# CONNECTORS_SELECTORS.net
KiCad netlist of a schematic drawn in Altium Designer
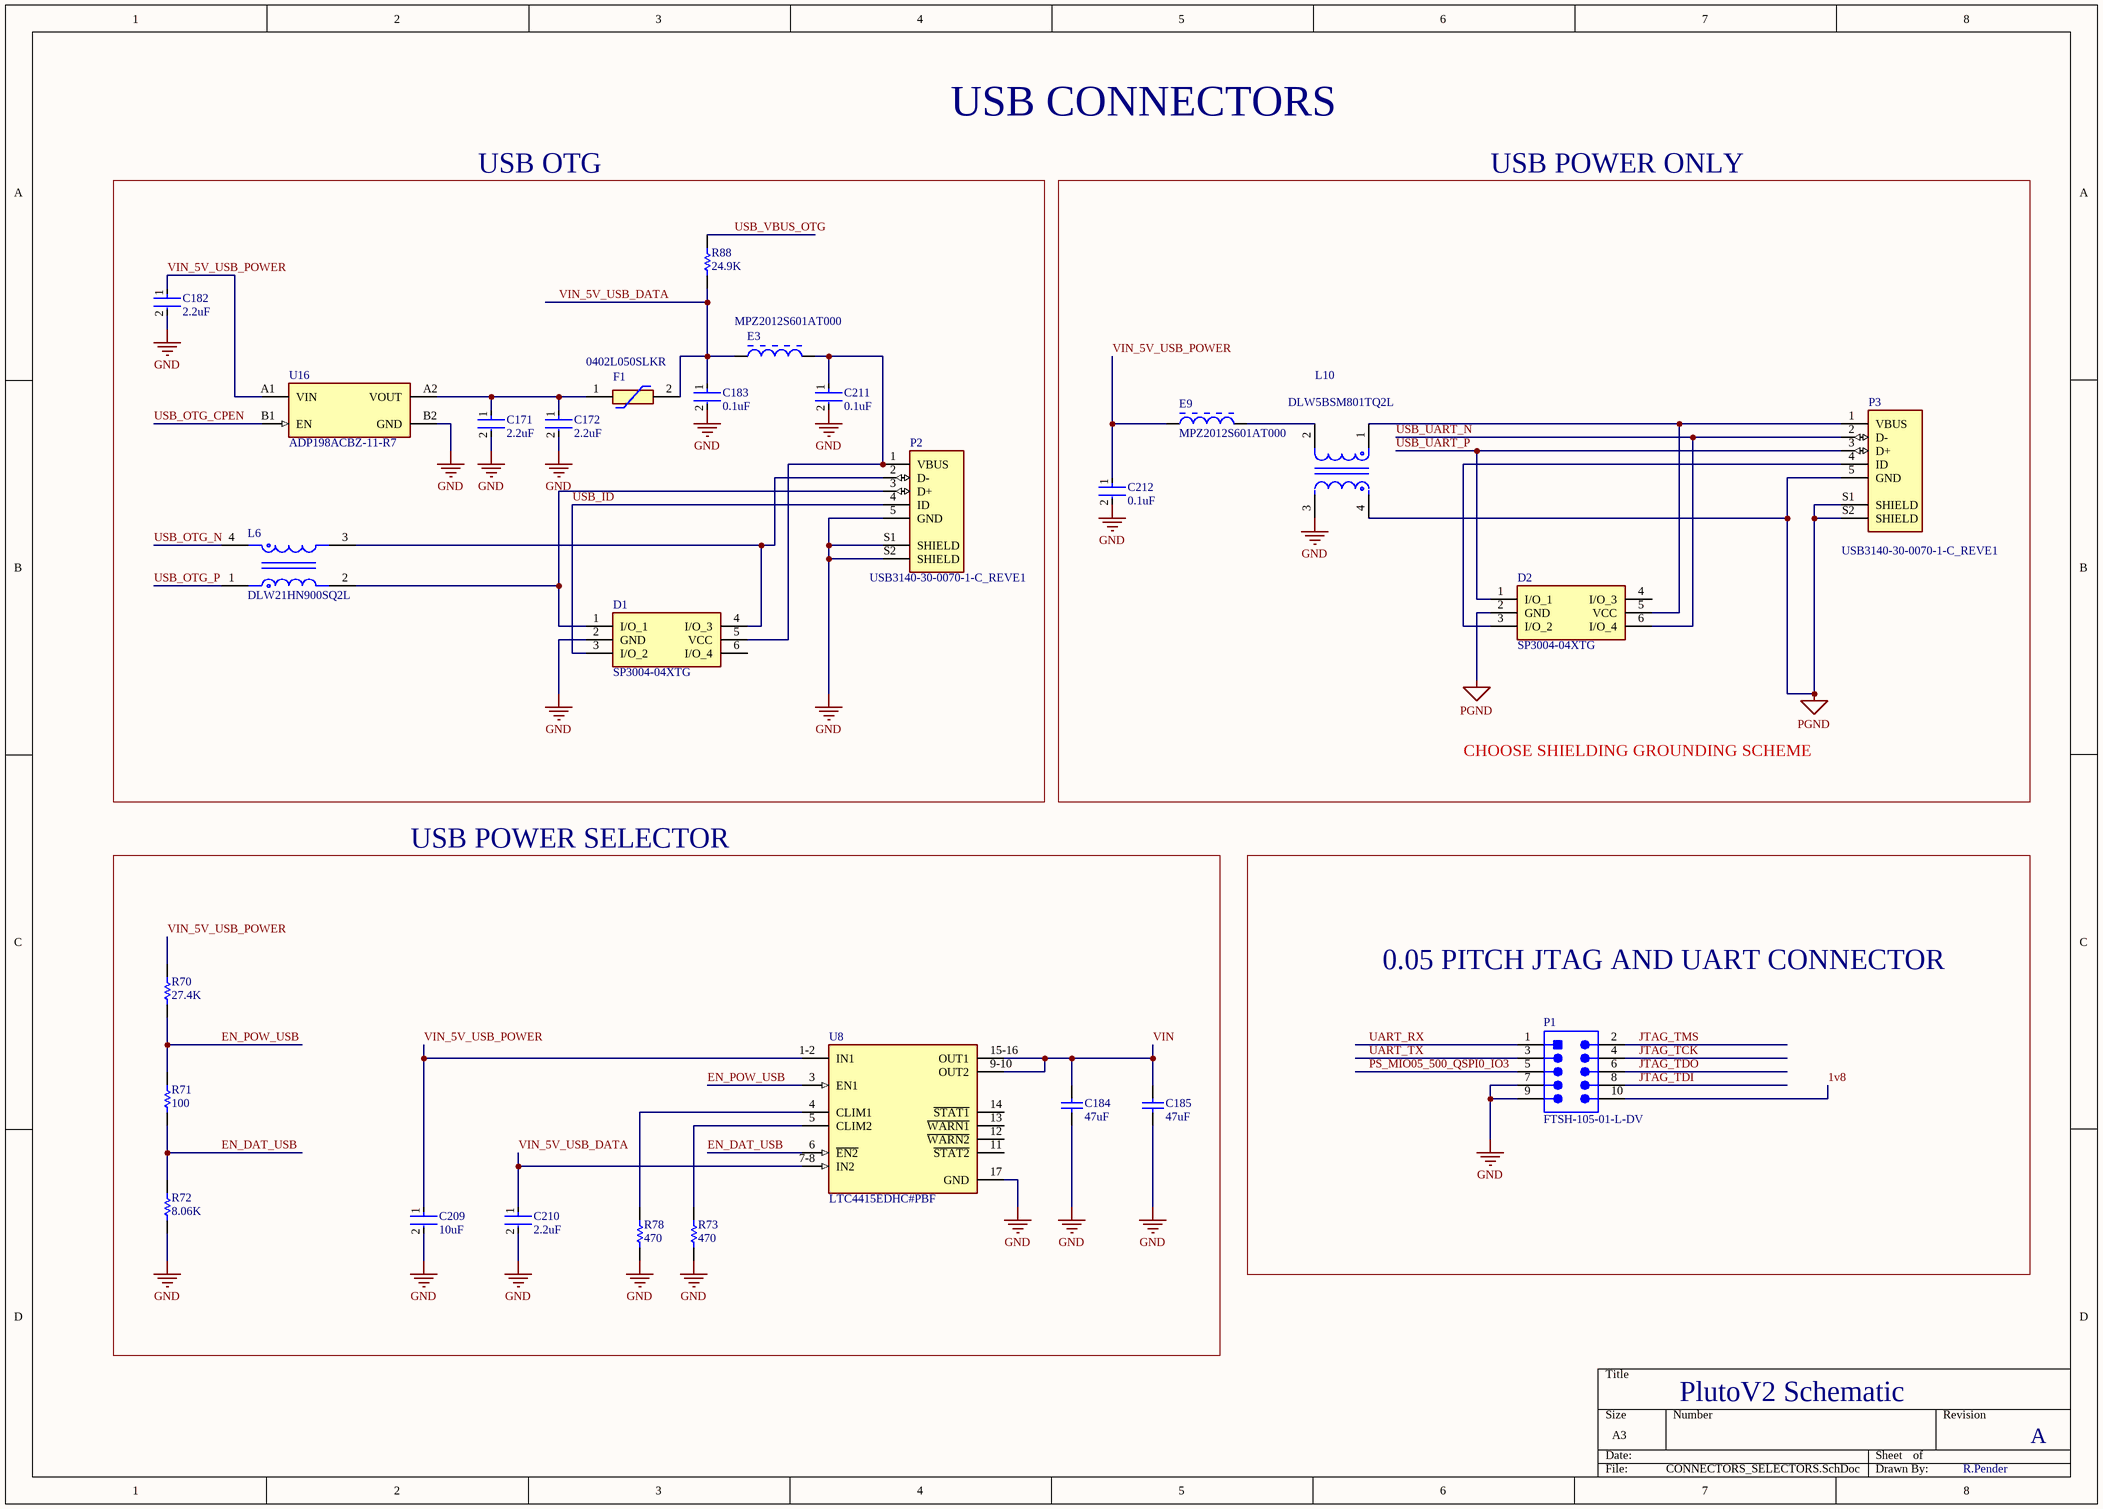
[diagram p0: CONNECTORS_SELECTORS.SchDoc]

(export (version "E")
  (design (tool "Eeschema 10.0.6"))
  (components
    (comp (ref "C171")
      (value "2.2uF")
      (footprint "FP-GRM188-0_2-IPC_C")
      (description "Chip Multilayer Ceramic Capacitors for General Purpose, 0603, 2.2uF, X5R, 15%, 10%, 50V")
      (fields (field (name "TOLERANCE") "10%"))
      (libsource (lib "Altium Content Vault") (part "11868f565c42a9108669ba33697ecf6"))
    )
    (comp (ref "C172")
      (value "2.2uF")
      (footprint "FP-GRM188-0_2-IPC_C")
      (description "Chip Multilayer Ceramic Capacitors for General Purpose, 0603, 2.2uF, X5R, 15%, 10%, 50V")
      (fields (field (name "TOLERANCE") "10%"))
      (libsource (lib "Altium Content Vault") (part "11868f565c42a9108669ba33697ecf6"))
    )
    (comp (ref "C182")
      (value "2.2uF")
      (footprint "FP-GRM188-0_2-MFG")
      (description "Chip Multilayer Ceramic Capacitors for General Purpose, 0603, 2.2uF, X5R, 15%, 10%, 50V")
      (fields (field (name "TOLERANCE") "10%"))
      (libsource (lib "Altium Content Vault") (part "11868f565c42a9108669ba33697ecf6"))
    )
    (comp (ref "C183")
      (value "0.1uF")
      (footprint "FP-CL10-IPC_A")
      (description "Cap Ceramic 100nF 100V X7R ±10% Pad SMD 0603 +125°C T/R")
      (fields (field (name "TOLERANCE") "10%"))
      (libsource (lib "Altium Content Vault") (part "b4654b650e69147ec39a6b967a45e02"))
    )
    (comp (ref "C184")
      (value "47uF")
      (footprint "TAYO-JMK212BBJ476MG-T_L")
      (fields
        (field (name "MANUFACTURER") "Taiyo Yuden")
        (field (name "TOLERANCE") "±20%")
        (field (name "PCN PART NUMBER") "X5R,X7RDielectrics23/Jan/2008")
      )
      (libsource (lib "Altium Content Vault") (part "CAP-NP-2"))
    )
    (comp (ref "C185")
      (value "47uF")
      (footprint "TAYO-JMK212BBJ476MG-T_L")
      (fields
        (field (name "MANUFACTURER") "Taiyo Yuden")
        (field (name "TOLERANCE") "±20%")
        (field (name "PCN PART NUMBER") "X5R,X7RDielectrics23/Jan/2008")
      )
      (libsource (lib "Altium Content Vault") (part "CAP-NP-2"))
    )
    (comp (ref "C209")
      (value "10uF")
      (footprint "FP-GRM188-0_15-MFG")
      (description "Chip Multilayer Ceramic Capacitors for General Purpose, 0603, 10uF, X5R, 15%, 20%, 10V")
      (fields (field (name "TOLERANCE") "20%"))
      (libsource (lib "Altium Content Vault") (part "02cd4be3c70576c341d710602a673aa"))
    )
    (comp (ref "C210")
      (value "2.2uF")
      (footprint "FP-GRM188-0_2-IPC_C")
      (description "Chip Multilayer Ceramic Capacitors for General Purpose, 0603, 2.2uF, X5R, 15%, 10%, 50V")
      (fields (field (name "TOLERANCE") "10%"))
      (libsource (lib "Altium Content Vault") (part "11868f565c42a9108669ba33697ecf6"))
    )
    (comp (ref "C211")
      (value "0.1uF")
      (footprint "FP-CL10-IPC_A")
      (description "Cap Ceramic 100nF 100V X7R ±10% Pad SMD 0603 +125°C T/R")
      (fields (field (name "TOLERANCE") "10%"))
      (libsource (lib "Altium Content Vault") (part "b4654b650e69147ec39a6b967a45e02"))
    )
    (comp (ref "C212")
      (value "0.1uF")
      (footprint "FP-CL10-IPC_A")
      (description "Cap Ceramic 100nF 100V X7R ±10% Pad SMD 0603 +125°C T/R")
      (fields (field (name "TOLERANCE") "10%"))
      (libsource (lib "Altium Content Vault") (part "b4654b650e69147ec39a6b967a45e02"))
    )
    (comp (ref "D1")
      (value "SP3004-04XTG")
      (footprint "SamacSys:SOTFL50P160X60-6N")
      (description "TVS Diode (Uni-directional)")
      (libsource (lib "*") (part "SP3004-04XTG"))
    )
    (comp (ref "D2")
      (value "SP3004-04XTG")
      (footprint "SamacSys:SOTFL50P160X60-6N")
      (description "TVS Diode (Uni-directional)")
      (libsource (lib "*") (part "SP3004-04XTG"))
    )
    (comp (ref "E3")
      (value "MPZ2012S601AT000")
      (footprint "TDK-MPZ2012_V")
      (description "Chip Bead, 0.1 Ohm, 2 A, -55 to 125 degC, 2-Pin SMD (0805), RoHS, Tape and Reel")
      (fields (field (name "PCN PART NUMBER") "MMZ,MPSSeriesOct/2014") (field (name "MANUFACTURER") "TDK"))
      (libsource (lib "Altium Content Vault") (part "BEAD-2"))
    )
    (comp (ref "E9")
      (value "MPZ2012S601AT000")
      (footprint "TDK-MPZ2012_V")
      (description "Chip Bead, 0.1 Ohm, 2 A, -55 to 125 degC, 2-Pin SMD (0805), RoHS, Tape and Reel")
      (fields (field (name "PCN PART NUMBER") "MMZ,MPSSeriesOct/2014") (field (name "MANUFACTURER") "TDK"))
      (libsource (lib "Altium Content Vault") (part "BEAD-2"))
    )
    (comp (ref "F1")
      (value "0402L050SLKR")
      (footprint "SamacSys:0402L010SLKR")
      (description "Resettable Fuse")
      (libsource (lib "*") (part "0402L050SLKR"))
    )
    (comp (ref "L6")
      (value "DLW21HN900SQ2L")
      (footprint "FP-DLW21HN-MFG")
      (description "CMC 330MA 2LN 90 OHM SMD")
      (fields (field (name "TOLERANCE") "25%"))
      (libsource (lib "Altium Content Vault") (part "0a69a9865a8fa8fb197e9315ef85d0a"))
    )
    (comp (ref "L10")
      (value "DLW5BSM801TQ2L")
      (footprint "FP-DLW5BS-MFG")
      (description "Common Mode Choke, 2020, 800Ω @ 100MHz, 0.056Ω, 40%, 2A")
      (fields (field (name "TOLERANCE") "40%"))
      (libsource (lib "Altium Content Vault") (part "7e18bf8fdb9f2485ca2bcdf9073d69f"))
    )
    (comp (ref "P1")
      (value "FTSH-105-01-L-DV")
      (footprint "SMTC-FTSH-105-01-L-DV_V")
      (description "Male Header, Pitch 1.27 mm, 2 x 5 Position, Height 5.96 mm, -55 to 125 degC, RoHS, Bulk")
      (fields (field (name "MANUFACTURER") "Samtec"))
      (libsource (lib "Altium Content Vault") (part "CN-2P-M-R10"))
    )
    (comp (ref "P2")
      (value "USB3140-30-0070-1-C_REVE1")
      (footprint "GCT_USB3140-30-0070-1-C_REVE1")
      (fields (field (name "MF") "Global Connector Technology") (field (name "MP") "USB3140-30-0070-1-C"))
      (libsource (lib "USB3140-30-0070-1-C_REVE1") (part "USB3140-30-0070-1-C_REVE1"))
    )
    (comp (ref "P3")
      (value "USB3140-30-0070-1-C_REVE1")
      (footprint "GCT_USB3140-30-0070-1-C_REVE1")
      (fields (field (name "MF") "Global Connector Technology") (field (name "MP") "USB3140-30-0070-1-C"))
      (libsource (lib "USB3140-30-0070-1-C_REVE1") (part "USB3140-30-0070-1-C_REVE1"))
    )
    (comp (ref "R70")
      (value "27.4K")
      (footprint "2-0402")
      (fields (field (name "PUBLISHER") "Altium Limited"))
      (libsource (lib "Panasonic Resistor") (part "ERJ2RK"))
    )
    (comp (ref "R71")
      (value "100")
      (footprint "2-0402")
      (fields (field (name "PUBLISHER") "Altium Limited"))
      (libsource (lib "Panasonic Resistor") (part "ERJ2RK"))
    )
    (comp (ref "R72")
      (value "8.06K")
      (footprint "2-0402")
      (fields (field (name "PUBLISHER") "Altium Limited"))
      (libsource (lib "Panasonic Resistor") (part "ERJ2RK"))
    )
    (comp (ref "R73")
      (value "470")
      (footprint "RESC1005X40X25ML05T10")
      (fields (field (name "PART NUMBER") "RC0402FR-07470RL") (field (name "MANUFACTURER") "Yageo / Phycomp"))
      (libsource (lib "Altium Content Vault") (part "RES"))
    )
    (comp (ref "R78")
      (value "470")
      (footprint "RESC1005X40X25ML05T10")
      (fields (field (name "PART NUMBER") "RC0402FR-07470RL") (field (name "MANUFACTURER") "Yageo / Phycomp"))
      (libsource (lib "Altium Content Vault") (part "RES"))
    )
    (comp (ref "R88")
      (value "24.9K")
      (footprint "2-0402")
      (fields (field (name "PUBLISHER") "Altium Limited"))
      (libsource (lib "Panasonic Resistor") (part "ERJ2RK"))
    )
    (comp (ref "U8")
      (value "LTC4415EDHC#PBF")
      (footprint "FP-DHC-16-05-08-1872-MFG")
      (description "IC OR CTRLR SRC SELECT 16DFN")
      (libsource (lib "Altium Content Vault") (part "3ca062e251a206593296efba02ab3fb"))
    )
    (comp (ref "U16")
      (value "ADP198ACBZ-11-R7")
      (footprint "FP-CB-4-4-MFG")
      (description "IC PWR SWITCH P-CHAN 1:1 4WLCSP")
      (libsource (lib "Altium Content Vault") (part "e79baadf0d63db38dbad7ddd3c26481"))
    )
  )
  (nets
    (net (code "1") (name "/1v8") (class "Default")
      (node (ref "P1") (pin "10") (pinfunction "10_10") (pintype "passive"))
    )
    (net (code "2") (name "/EN_DAT_USB") (class "Default")
      (node (ref "R71") (pin "2") (pinfunction "2_2") (pintype "passive"))
      (node (ref "R72") (pin "1") (pinfunction "1_1") (pintype "passive"))
      (node (ref "U8") (pin "6") (pinfunction "~{EN2}_6") (pintype "input"))
    )
    (net (code "3") (name "/EN_POW_USB") (class "Default")
      (node (ref "R70") (pin "2") (pinfunction "2_2") (pintype "passive"))
      (node (ref "R71") (pin "1") (pinfunction "1_1") (pintype "passive"))
      (node (ref "U8") (pin "3") (pinfunction "EN1_3") (pintype "input"))
    )
    (net (code "4") (name "/JTAG_TCK") (class "Default")
      (node (ref "P1") (pin "4") (pinfunction "4_4") (pintype "passive"))
    )
    (net (code "5") (name "/JTAG_TDI") (class "Default")
      (node (ref "P1") (pin "8") (pinfunction "8_8") (pintype "passive"))
    )
    (net (code "6") (name "/JTAG_TDO") (class "Default")
      (node (ref "P1") (pin "6") (pinfunction "6_6") (pintype "passive"))
    )
    (net (code "7") (name "/JTAG_TMS") (class "Default")
      (node (ref "P1") (pin "2") (pinfunction "2_2") (pintype "passive"))
    )
    (net (code "8") (name "/PS_MIO05_500_QSPI0_IO3") (class "Default")
      (node (ref "P1") (pin "5") (pinfunction "5_5") (pintype "passive"))
    )
    (net (code "9") (name "/UART_RX") (class "Default")
      (node (ref "P1") (pin "1") (pinfunction "1_1") (pintype "passive"))
    )
    (net (code "10") (name "/UART_TX") (class "Default")
      (node (ref "P1") (pin "3") (pinfunction "3_3") (pintype "passive"))
    )
    (net (code "11") (name "/USB_ID") (class "Default")
      (node (ref "D1") (pin "3") (pinfunction "I/O_2_3") (pintype "passive"))
      (node (ref "P2") (pin "4") (pinfunction "ID_4") (pintype "passive"))
    )
    (net (code "12") (name "/USB_OTG_CPEN") (class "Default")
      (node (ref "U16") (pin "B1") (pinfunction "EN_B1") (pintype "input"))
    )
    (net (code "13") (name "/USB_OTG_N") (class "Default")
      (node (ref "L6") (pin "4") (pinfunction "4_4") (pintype "passive"))
    )
    (net (code "14") (name "/USB_OTG_P") (class "Default")
      (node (ref "L6") (pin "1") (pinfunction "1_1") (pintype "passive"))
    )
    (net (code "15") (name "/USB_UART_N") (class "Default")
      (node (ref "D2") (pin "6") (pinfunction "I/O_4_6") (pintype "passive"))
      (node (ref "P3") (pin "2") (pinfunction "D-_2") (pintype "bidirectional"))
    )
    (net (code "16") (name "/USB_UART_P") (class "Default")
      (node (ref "D2") (pin "1") (pinfunction "I/O_1_1") (pintype "passive"))
      (node (ref "P3") (pin "3") (pinfunction "D+_3") (pintype "bidirectional"))
    )
    (net (code "17") (name "/USB_VBUS_OTG") (class "Default")
      (node (ref "R88") (pin "2") (pinfunction "2_2") (pintype "passive"))
    )
    (net (code "18") (name "/VIN") (class "Default")
      (node (ref "C184") (pin "1") (pinfunction "1_1") (pintype "passive"))
      (node (ref "C185") (pin "1") (pinfunction "1_1") (pintype "passive"))
      (node (ref "U8") (pin "15-16") (pinfunction "OUT1_15-16") (pintype "passive"))
      (node (ref "U8") (pin "9-10") (pinfunction "OUT2_9-10") (pintype "passive"))
    )
    (net (code "19") (name "/VIN_5V_USB_DATA") (class "Default")
      (node (ref "C183") (pin "1") (pinfunction "1_1") (pintype "passive"))
      (node (ref "C210") (pin "1") (pinfunction "1_1") (pintype "passive"))
      (node (ref "E3") (pin "1") (pinfunction "1_1") (pintype "passive"))
      (node (ref "F1") (pin "2") (pinfunction "2_2") (pintype "passive"))
      (node (ref "R88") (pin "1") (pinfunction "1_1") (pintype "passive"))
      (node (ref "U8") (pin "7-8") (pinfunction "IN2_7-8") (pintype "input"))
    )
    (net (code "20") (name "/VIN_5V_USB_POWER") (class "Default")
      (node (ref "C182") (pin "1") (pinfunction "1_1") (pintype "passive"))
      (node (ref "C209") (pin "1") (pinfunction "1_1") (pintype "passive"))
      (node (ref "C212") (pin "1") (pinfunction "1_1") (pintype "passive"))
      (node (ref "E9") (pin "1") (pinfunction "1_1") (pintype "passive"))
      (node (ref "R70") (pin "1") (pinfunction "1_1") (pintype "passive"))
      (node (ref "U16") (pin "A1") (pinfunction "VIN_A1") (pintype "power_in"))
      (node (ref "U8") (pin "1-2") (pinfunction "IN1_1-2") (pintype "power_in"))
    )
    (net (code "21") (name "GND") (class "Default")
      (node (ref "C171") (pin "2") (pinfunction "2_2") (pintype "passive"))
      (node (ref "C172") (pin "2") (pinfunction "2_2") (pintype "passive"))
      (node (ref "C182") (pin "2") (pinfunction "2_2") (pintype "passive"))
      (node (ref "C183") (pin "2") (pinfunction "2_2") (pintype "passive"))
      (node (ref "C184") (pin "2") (pinfunction "2_2") (pintype "passive"))
      (node (ref "C185") (pin "2") (pinfunction "2_2") (pintype "passive"))
      (node (ref "C209") (pin "2") (pinfunction "2_2") (pintype "passive"))
      (node (ref "C210") (pin "2") (pinfunction "2_2") (pintype "passive"))
      (node (ref "C211") (pin "2") (pinfunction "2_2") (pintype "passive"))
      (node (ref "C212") (pin "2") (pinfunction "2_2") (pintype "passive"))
      (node (ref "D1") (pin "2") (pinfunction "GND_2") (pintype "passive"))
      (node (ref "L10") (pin "3") (pinfunction "3_3") (pintype "passive"))
      (node (ref "P1") (pin "7") (pinfunction "7_7") (pintype "passive"))
      (node (ref "P1") (pin "9") (pinfunction "9_9") (pintype "passive"))
      (node (ref "P2") (pin "5") (pinfunction "GND_5") (pintype "power_in"))
      (node (ref "P2") (pin "S1") (pinfunction "SHIELD_S1") (pintype "passive"))
      (node (ref "P2") (pin "S2") (pinfunction "SHIELD_S2") (pintype "passive"))
      (node (ref "R72") (pin "2") (pinfunction "2_2") (pintype "passive"))
      (node (ref "R73") (pin "2") (pinfunction "2_2") (pintype "passive"))
      (node (ref "R78") (pin "2") (pinfunction "2_2") (pintype "passive"))
      (node (ref "U16") (pin "B2") (pinfunction "GND_B2") (pintype "power_in"))
      (node (ref "U8") (pin "17") (pinfunction "GND_17") (pintype "power_in"))
    )
    (net (code "22") (name "Net-(D1-I{slash}O_1)") (class "Default")
      (node (ref "D1") (pin "1") (pinfunction "I/O_1_1") (pintype "passive"))
      (node (ref "L6") (pin "2") (pinfunction "2_2") (pintype "passive"))
      (node (ref "P2") (pin "3") (pinfunction "D+_3") (pintype "bidirectional"))
    )
    (net (code "23") (name "Net-(D1-I{slash}O_3)") (class "Default")
      (node (ref "D1") (pin "4") (pinfunction "I/O_3_4") (pintype "passive"))
      (node (ref "L6") (pin "3") (pinfunction "3_3") (pintype "passive"))
      (node (ref "P2") (pin "2") (pinfunction "D-_2") (pintype "bidirectional"))
    )
    (net (code "24") (name "Net-(D1-VCC)") (class "Default")
      (node (ref "C211") (pin "1") (pinfunction "1_1") (pintype "passive"))
      (node (ref "D1") (pin "5") (pinfunction "VCC_5") (pintype "passive"))
      (node (ref "E3") (pin "2") (pinfunction "2_2") (pintype "passive"))
      (node (ref "P2") (pin "1") (pinfunction "VBUS_1") (pintype "power_in"))
    )
    (net (code "25") (name "Net-(D2-I{slash}O_2)") (class "Default")
      (node (ref "D2") (pin "3") (pinfunction "I/O_2_3") (pintype "passive"))
      (node (ref "P3") (pin "4") (pinfunction "ID_4") (pintype "passive"))
    )
    (net (code "26") (name "Net-(D2-VCC)") (class "Default")
      (node (ref "D2") (pin "5") (pinfunction "VCC_5") (pintype "passive"))
      (node (ref "L10") (pin "1") (pinfunction "1_1") (pintype "passive"))
      (node (ref "P3") (pin "1") (pinfunction "VBUS_1") (pintype "power_in"))
    )
    (net (code "27") (name "Net-(E9-Pad2)") (class "Default")
      (node (ref "E9") (pin "2") (pinfunction "2_2") (pintype "passive"))
      (node (ref "L10") (pin "2") (pinfunction "2_2") (pintype "passive"))
    )
    (net (code "28") (name "Net-(U8-CLIM1)") (class "Default")
      (node (ref "R78") (pin "1") (pinfunction "1_1") (pintype "passive"))
      (node (ref "U8") (pin "4") (pinfunction "CLIM1_4") (pintype "passive"))
    )
    (net (code "29") (name "Net-(U8-CLIM2)") (class "Default")
      (node (ref "R73") (pin "1") (pinfunction "1_1") (pintype "passive"))
      (node (ref "U8") (pin "5") (pinfunction "CLIM2_5") (pintype "passive"))
    )
    (net (code "30") (name "Net-(U16-VOUT)") (class "Default")
      (node (ref "C171") (pin "1") (pinfunction "1_1") (pintype "passive"))
      (node (ref "C172") (pin "1") (pinfunction "1_1") (pintype "passive"))
      (node (ref "F1") (pin "1") (pinfunction "1_1") (pintype "passive"))
      (node (ref "U16") (pin "A2") (pinfunction "VOUT_A2") (pintype "passive"))
    )
    (net (code "31") (name "PGND") (class "Default")
      (node (ref "D2") (pin "2") (pinfunction "GND_2") (pintype "passive"))
      (node (ref "L10") (pin "4") (pinfunction "4_4") (pintype "passive"))
      (node (ref "P3") (pin "5") (pinfunction "GND_5") (pintype "power_in"))
      (node (ref "P3") (pin "S1") (pinfunction "SHIELD_S1") (pintype "passive"))
      (node (ref "P3") (pin "S2") (pinfunction "SHIELD_S2") (pintype "passive"))
    )
    (net (code "32") (name "unconnected-(D1-I{slash}O_4-Pad6)") (class "Default")
      (node (ref "D1") (pin "6") (pinfunction "I/O_4_6") (pintype "passive"))
    )
    (net (code "33") (name "unconnected-(D2-I{slash}O_3-Pad4)") (class "Default")
      (node (ref "D2") (pin "4") (pinfunction "I/O_3_4") (pintype "passive"))
    )
    (net (code "34") (name "unconnected-(U8-~{STAT1}-Pad14)") (class "Default")
      (node (ref "U8") (pin "14") (pinfunction "~{STAT1}_14") (pintype "open_collector"))
    )
    (net (code "35") (name "unconnected-(U8-~{STAT2}-Pad11)") (class "Default")
      (node (ref "U8") (pin "11") (pinfunction "~{STAT2}_11") (pintype "open_collector"))
    )
    (net (code "36") (name "unconnected-(U8-~{WARN1}-Pad13)") (class "Default")
      (node (ref "U8") (pin "13") (pinfunction "~{WARN1}_13") (pintype "passive"))
    )
    (net (code "37") (name "unconnected-(U8-~{WARN2}-Pad12)") (class "Default")
      (node (ref "U8") (pin "12") (pinfunction "~{WARN2}_12") (pintype "passive"))
    )
  )
)
